# LCD_NOKIA1616.net
KiCad netlist of a schematic drawn in Altium Designer
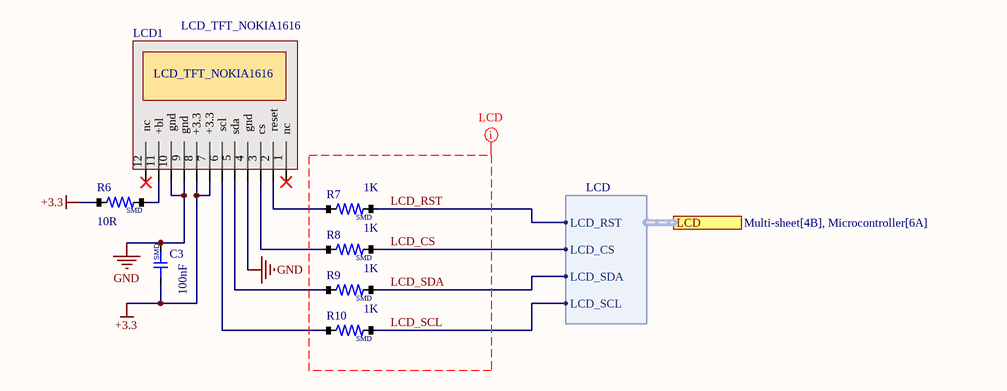
[diagram p0: LCD_NOKIA1616.SchDoc]

(export (version "E")
  (design (tool "Eeschema 10.0.6"))
  (components
    (comp (ref "C3") (value "100nF") (footprint "CAP-0805") (libsource (lib "kave-eng-pro") (part "cap_smd")))
    (comp (ref "LCD1")
      (value "LCD_TFT_NOKIA1616")
      (footprint "lcd1616-flat")
      (libsource (lib "kave-eng-pro") (part "lcd_nokia1616"))
    )
    (comp (ref "R6") (value "10R") (footprint "RES/0805") (libsource (lib "kave-eng-pro") (part "RES/SMD")))
    (comp (ref "R7") (value "1K") (footprint "RES/0805") (libsource (lib "kave-eng-pro") (part "RES/SMD")))
    (comp (ref "R8") (value "1K") (footprint "RES/0805") (libsource (lib "kave-eng-pro") (part "RES/SMD")))
    (comp (ref "R9") (value "1K") (footprint "RES/0805") (libsource (lib "kave-eng-pro") (part "RES/SMD")))
    (comp (ref "R10") (value "1K") (footprint "RES/0805") (libsource (lib "kave-eng-pro") (part "RES/SMD")))
  )
  (nets
    (net (code "2") (name "+3.3") (class "Default")
      (node (ref "C3") (pin "1") (pintype "passive"))
      (node (ref "LCD1") (pin "7") (pinfunction "+3.3_7") (pintype "passive"))
      (node (ref "LCD1") (pin "8") (pinfunction "+3.3_8") (pintype "passive"))
      (node (ref "R6") (pin "1") (pinfunction "1_1") (pintype "passive"))
    )
    (net (code "3") (name "/LCD_CS") (class "Default")
      (node (ref "R8") (pin "2") (pinfunction "2_2") (pintype "passive"))
    )
    (net (code "4") (name "/LCD_RST") (class "Default")
      (node (ref "R7") (pin "2") (pinfunction "2_2") (pintype "passive"))
    )
    (net (code "5") (name "/LCD_SCL") (class "Default")
      (node (ref "R10") (pin "2") (pinfunction "2_2") (pintype "passive"))
    )
    (net (code "6") (name "/LCD_SDA") (class "Default")
      (node (ref "R9") (pin "2") (pinfunction "2_2") (pintype "passive"))
    )
    (net (code "8") (name "GND") (class "Default")
      (node (ref "C3") (pin "2") (pintype "passive"))
      (node (ref "LCD1") (pin "10") (pinfunction "_gnd_10") (pintype "passive"))
      (node (ref "LCD1") (pin "4") (pinfunction "_gnd_4") (pintype "passive"))
      (node (ref "LCD1") (pin "9") (pinfunction "gnd_9") (pintype "passive"))
    )
    (net (code "9") (name "Net-(LCD1-+bl)") (class "Default")
      (node (ref "LCD1") (pin "11") (pinfunction "+bl_11") (pintype "passive"))
      (node (ref "R6") (pin "2") (pinfunction "2_2") (pintype "passive"))
    )
    (net (code "10") (name "Net-(LCD1-_reset)") (class "Default")
      (node (ref "LCD1") (pin "2") (pinfunction "_reset_2") (pintype "passive"))
      (node (ref "R7") (pin "1") (pinfunction "1_1") (pintype "passive"))
    )
    (net (code "11") (name "Net-(LCD1-_scl)") (class "Default")
      (node (ref "LCD1") (pin "6") (pinfunction "_scl_6") (pintype "passive"))
      (node (ref "R10") (pin "1") (pinfunction "1_1") (pintype "passive"))
    )
    (net (code "12") (name "Net-(LCD1-cs)") (class "Default")
      (node (ref "LCD1") (pin "3") (pinfunction "cs_3") (pintype "passive"))
      (node (ref "R8") (pin "1") (pinfunction "1_1") (pintype "passive"))
    )
    (net (code "13") (name "Net-(LCD1-sda)") (class "Default")
      (node (ref "LCD1") (pin "5") (pinfunction "sda_5") (pintype "passive"))
      (node (ref "R9") (pin "1") (pinfunction "1_1") (pintype "passive"))
    )
    (net (code "14") (name "unconnected-(LCD1-_nc-Pad12)") (class "Default")
      (node (ref "LCD1") (pin "12") (pinfunction "_nc_12") (pintype "passive+no_connect"))
    )
    (net (code "15") (name "unconnected-(LCD1-nc-Pad1)") (class "Default")
      (node (ref "LCD1") (pin "1") (pinfunction "nc_1") (pintype "passive+no_connect"))
    )
  )
)
